# lab.net
KiCad netlist of a schematic drawn in EAGLE
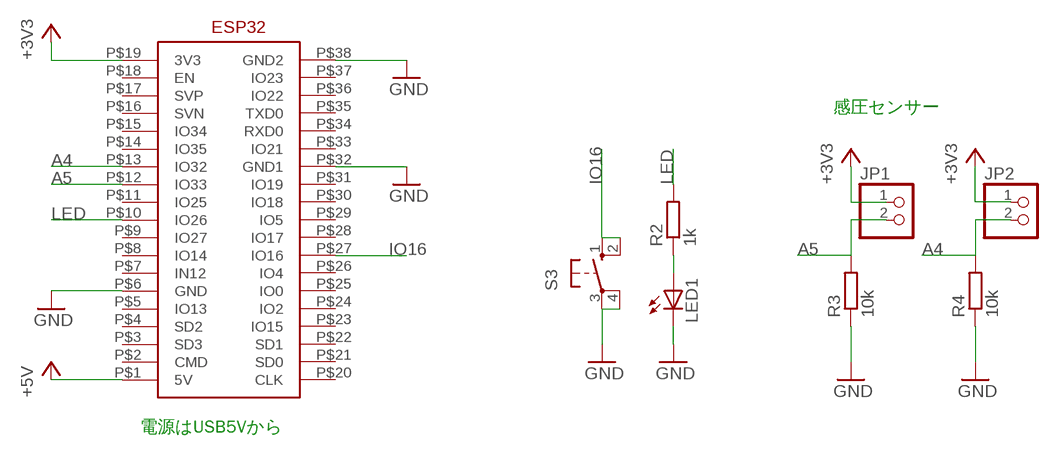
[diagram p0: schematic, sheet 1]

(export (version "E")
  (design (tool "Eeschema 10.0.6"))
  (components
    (comp (ref "JP1")
      (value "PINHD-1X2")
      (footprint "eagle-import:1X02")
      (libsource (lib "eagle-import") (part "PINHD-1X2"))
    )
    (comp (ref "JP2")
      (value "PINHD-1X2")
      (footprint "eagle-import:1X02")
      (libsource (lib "eagle-import") (part "PINHD-1X2"))
    )
    (comp (ref "LED1")
      (value "LEDSML0603")
      (footprint "eagle-import:SML0603")
      (libsource (lib "eagle-import") (part "LEDSML0603"))
    )
    (comp (ref "R2")
      (value "1k")
      (footprint "eagle-import:0207_10")
      (libsource (lib "eagle-import") (part "R-EU_0207/10"))
    )
    (comp (ref "R3")
      (value "10k")
      (footprint "eagle-import:0207_10")
      (libsource (lib "eagle-import") (part "R-EU_0207/10"))
    )
    (comp (ref "R4")
      (value "10k")
      (footprint "eagle-import:0207_10")
      (libsource (lib "eagle-import") (part "R-EU_0207/10"))
    )
    (comp (ref "S3")
      (value "10-XX")
      (footprint "eagle-import:B3F-10XX")
      (fields (field (name "MPN") "B3F-1000"))
      (libsource (lib "eagle-import") (part "10-XX"))
    )
    (comp (ref "U$1")
      (value "ESP32_DEVKITC")
      (footprint "eagle-import:ESP32_DEVKITC")
      (libsource (lib "eagle-import") (part "ESP32_DEVKITC"))
    )
  )
  (nets
    (net (code "1") (name "+3V3") (class "Default")
      (node (ref "JP1") (pin "1") (pinfunction "1_1") (pintype "passive"))
      (node (ref "JP2") (pin "1") (pinfunction "1_1") (pintype "passive"))
      (node (ref "U$1") (pin "P$19") (pinfunction "3V3_P$19") (pintype "bidirectional"))
    )
    (net (code "2") (name "+5V") (class "Default")
      (node (ref "U$1") (pin "P$1") (pinfunction "5V_P$1") (pintype "bidirectional"))
    )
    (net (code "3") (name "/A4") (class "Default")
      (node (ref "JP2") (pin "2") (pinfunction "2_2") (pintype "passive"))
      (node (ref "R4") (pin "2") (pinfunction "2_2") (pintype "passive"))
      (node (ref "U$1") (pin "P$13") (pinfunction "IO32_P$13") (pintype "bidirectional"))
    )
    (net (code "4") (name "/A5") (class "Default")
      (node (ref "JP1") (pin "2") (pinfunction "2_2") (pintype "passive"))
      (node (ref "R3") (pin "2") (pinfunction "2_2") (pintype "passive"))
      (node (ref "U$1") (pin "P$12") (pinfunction "IO33_P$12") (pintype "bidirectional"))
    )
    (net (code "5") (name "/IO16") (class "Default")
      (node (ref "S3") (pin "1") (pinfunction "S_1") (pintype "passive"))
      (node (ref "S3") (pin "2") (pinfunction "S1_2") (pintype "passive"))
      (node (ref "U$1") (pin "P$27") (pinfunction "IO16_P$27") (pintype "bidirectional"))
    )
    (net (code "6") (name "/LED") (class "Default")
      (node (ref "R2") (pin "2") (pinfunction "2_2") (pintype "passive"))
      (node (ref "U$1") (pin "P$10") (pinfunction "IO26_P$10") (pintype "bidirectional"))
    )
    (net (code "7") (name "GND") (class "Default")
      (node (ref "LED1") (pin "C") (pinfunction "C_C") (pintype "passive"))
      (node (ref "R3") (pin "1") (pinfunction "1_1") (pintype "passive"))
      (node (ref "R4") (pin "1") (pinfunction "1_1") (pintype "passive"))
      (node (ref "S3") (pin "3") (pinfunction "P_3") (pintype "passive"))
      (node (ref "S3") (pin "4") (pinfunction "P1_4") (pintype "passive"))
      (node (ref "U$1") (pin "P$32") (pinfunction "GND1_P$32") (pintype "bidirectional"))
      (node (ref "U$1") (pin "P$38") (pinfunction "GND2_P$38") (pintype "bidirectional"))
      (node (ref "U$1") (pin "P$6") (pinfunction "GND_P$6") (pintype "bidirectional"))
    )
    (net (code "8") (name "Net-(LED1-PadA)") (class "Default")
      (node (ref "LED1") (pin "A") (pinfunction "A_A") (pintype "passive"))
      (node (ref "R2") (pin "1") (pinfunction "1_1") (pintype "passive"))
    )
    (net (code "9") (name "unconnected-(U$1-CLK-PadP$20)") (class "Default")
      (node (ref "U$1") (pin "P$20") (pinfunction "CLK_P$20") (pintype "bidirectional"))
    )
    (net (code "10") (name "unconnected-(U$1-CMD-PadP$2)") (class "Default")
      (node (ref "U$1") (pin "P$2") (pinfunction "CMD_P$2") (pintype "bidirectional"))
    )
    (net (code "11") (name "unconnected-(U$1-EN-PadP$18)") (class "Default")
      (node (ref "U$1") (pin "P$18") (pinfunction "EN_P$18") (pintype "bidirectional"))
    )
    (net (code "12") (name "unconnected-(U$1-IN12-PadP$7)") (class "Default")
      (node (ref "U$1") (pin "P$7") (pinfunction "IN12_P$7") (pintype "bidirectional"))
    )
    (net (code "13") (name "unconnected-(U$1-IO0-PadP$25)") (class "Default")
      (node (ref "U$1") (pin "P$25") (pinfunction "IO0_P$25") (pintype "bidirectional"))
    )
    (net (code "14") (name "unconnected-(U$1-IO2-PadP$24)") (class "Default")
      (node (ref "U$1") (pin "P$24") (pinfunction "IO2_P$24") (pintype "bidirectional"))
    )
    (net (code "15") (name "unconnected-(U$1-IO4-PadP$26)") (class "Default")
      (node (ref "U$1") (pin "P$26") (pinfunction "IO4_P$26") (pintype "bidirectional"))
    )
    (net (code "16") (name "unconnected-(U$1-IO5-PadP$29)") (class "Default")
      (node (ref "U$1") (pin "P$29") (pinfunction "IO5_P$29") (pintype "bidirectional"))
    )
    (net (code "17") (name "unconnected-(U$1-IO13-PadP$5)") (class "Default")
      (node (ref "U$1") (pin "P$5") (pinfunction "IO13_P$5") (pintype "bidirectional"))
    )
    (net (code "18") (name "unconnected-(U$1-IO14-PadP$8)") (class "Default")
      (node (ref "U$1") (pin "P$8") (pinfunction "IO14_P$8") (pintype "bidirectional"))
    )
    (net (code "19") (name "unconnected-(U$1-IO15-PadP$23)") (class "Default")
      (node (ref "U$1") (pin "P$23") (pinfunction "IO15_P$23") (pintype "bidirectional"))
    )
    (net (code "20") (name "unconnected-(U$1-IO17-PadP$28)") (class "Default")
      (node (ref "U$1") (pin "P$28") (pinfunction "IO17_P$28") (pintype "bidirectional"))
    )
    (net (code "21") (name "unconnected-(U$1-IO18-PadP$30)") (class "Default")
      (node (ref "U$1") (pin "P$30") (pinfunction "IO18_P$30") (pintype "bidirectional"))
    )
    (net (code "22") (name "unconnected-(U$1-IO19-PadP$31)") (class "Default")
      (node (ref "U$1") (pin "P$31") (pinfunction "IO19_P$31") (pintype "bidirectional"))
    )
    (net (code "23") (name "unconnected-(U$1-IO21-PadP$33)") (class "Default")
      (node (ref "U$1") (pin "P$33") (pinfunction "IO21_P$33") (pintype "bidirectional"))
    )
    (net (code "24") (name "unconnected-(U$1-IO22-PadP$36)") (class "Default")
      (node (ref "U$1") (pin "P$36") (pinfunction "IO22_P$36") (pintype "bidirectional"))
    )
    (net (code "25") (name "unconnected-(U$1-IO23-PadP$37)") (class "Default")
      (node (ref "U$1") (pin "P$37") (pinfunction "IO23_P$37") (pintype "bidirectional"))
    )
    (net (code "26") (name "unconnected-(U$1-IO25-PadP$11)") (class "Default")
      (node (ref "U$1") (pin "P$11") (pinfunction "IO25_P$11") (pintype "bidirectional"))
    )
    (net (code "27") (name "unconnected-(U$1-IO27-PadP$9)") (class "Default")
      (node (ref "U$1") (pin "P$9") (pinfunction "IO27_P$9") (pintype "bidirectional"))
    )
    (net (code "28") (name "unconnected-(U$1-IO34-PadP$15)") (class "Default")
      (node (ref "U$1") (pin "P$15") (pinfunction "IO34_P$15") (pintype "bidirectional"))
    )
    (net (code "29") (name "unconnected-(U$1-IO35-PadP$14)") (class "Default")
      (node (ref "U$1") (pin "P$14") (pinfunction "IO35_P$14") (pintype "bidirectional"))
    )
    (net (code "30") (name "unconnected-(U$1-RXD0-PadP$34)") (class "Default")
      (node (ref "U$1") (pin "P$34") (pinfunction "RXD0_P$34") (pintype "bidirectional"))
    )
    (net (code "31") (name "unconnected-(U$1-SD0-PadP$21)") (class "Default")
      (node (ref "U$1") (pin "P$21") (pinfunction "SD0_P$21") (pintype "bidirectional"))
    )
    (net (code "32") (name "unconnected-(U$1-SD1-PadP$22)") (class "Default")
      (node (ref "U$1") (pin "P$22") (pinfunction "SD1_P$22") (pintype "bidirectional"))
    )
    (net (code "33") (name "unconnected-(U$1-SD2-PadP$4)") (class "Default")
      (node (ref "U$1") (pin "P$4") (pinfunction "SD2_P$4") (pintype "bidirectional"))
    )
    (net (code "34") (name "unconnected-(U$1-SD3-PadP$3)") (class "Default")
      (node (ref "U$1") (pin "P$3") (pinfunction "SD3_P$3") (pintype "bidirectional"))
    )
    (net (code "35") (name "unconnected-(U$1-SVN-PadP$16)") (class "Default")
      (node (ref "U$1") (pin "P$16") (pinfunction "SVN_P$16") (pintype "bidirectional"))
    )
    (net (code "36") (name "unconnected-(U$1-SVP-PadP$17)") (class "Default")
      (node (ref "U$1") (pin "P$17") (pinfunction "SVP_P$17") (pintype "bidirectional"))
    )
    (net (code "37") (name "unconnected-(U$1-TXD0-PadP$35)") (class "Default")
      (node (ref "U$1") (pin "P$35") (pinfunction "TXD0_P$35") (pintype "bidirectional"))
    )
  )
)
